# LED_Transmitter_2023_01_22_A.net
KiCad netlist of a schematic drawn in EAGLE
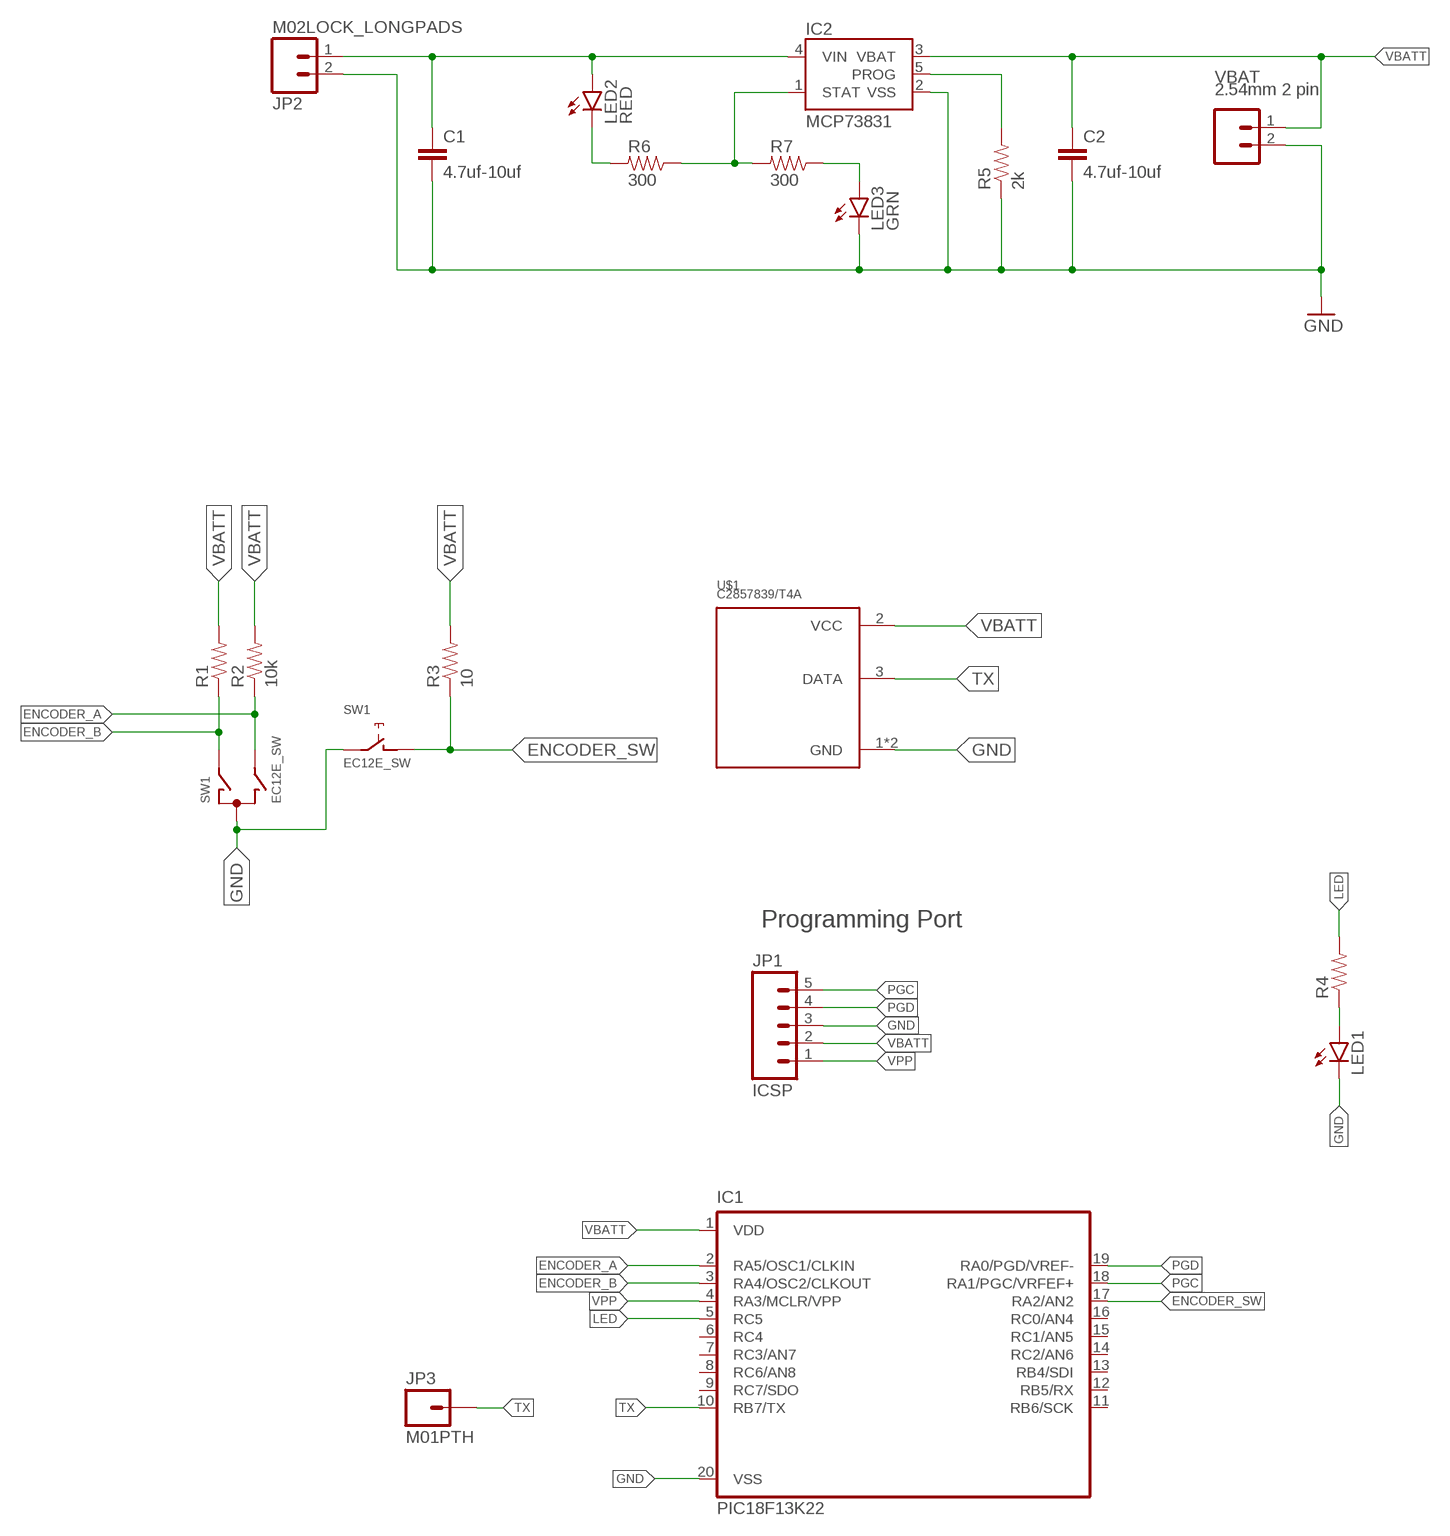
[diagram p0: schematic, sheet 1]

(export (version "E")
  (design (tool "Eeschema 10.0.6"))
  (components
    (comp (ref "C1")
      (value "4.7uf-10uf")
      (footprint "eagle-import:1206")
      (libsource (lib "eagle-import") (part "CAP1206"))
    )
    (comp (ref "C2")
      (value "4.7uf-10uf")
      (footprint "eagle-import:1206")
      (libsource (lib "eagle-import") (part "CAP1206"))
    )
    (comp (ref "IC1")
      (value "PIC18F13K22")
      (footprint "eagle-import:DIL20")
      (libsource (lib "eagle-import") (part "PIC18F13K22?"))
    )
    (comp (ref "IC2")
      (value "MCP73831")
      (footprint "eagle-import:SOT23-5")
      (libsource (lib "eagle-import") (part "MCP73831"))
    )
    (comp (ref "JP1")
      (value "ICSP")
      (footprint "eagle-import:1X05")
      (libsource (lib "eagle-import") (part "M05PTH"))
    )
    (comp (ref "JP2")
      (value "M02LOCK_LONGPADS")
      (footprint "eagle-import:1X02_LOCK_LONGPADS")
      (libsource (lib "eagle-import") (part "M02LOCK_LONGPADS"))
    )
    (comp (ref "JP3")
      (value "M01PTH")
      (footprint "eagle-import:1X01")
      (libsource (lib "eagle-import") (part "M01PTH"))
    )
    (comp (ref "LED1")
      (value "LED1206")
      (footprint "eagle-import:LED-1206")
      (libsource (lib "eagle-import") (part "LED1206"))
    )
    (comp (ref "LED2")
      (value "RED")
      (footprint "eagle-import:LED-1206")
      (libsource (lib "eagle-import") (part "LED1206"))
    )
    (comp (ref "LED3")
      (value "GRN")
      (footprint "eagle-import:LED-1206")
      (libsource (lib "eagle-import") (part "LED1206"))
    )
    (comp (ref "R1")
      (value "RESISTOR1206")
      (footprint "eagle-import:1206")
      (libsource (lib "eagle-import") (part "RESISTOR1206"))
    )
    (comp (ref "R2")
      (value "10k")
      (footprint "eagle-import:1206")
      (libsource (lib "eagle-import") (part "RESISTOR1206"))
    )
    (comp (ref "R3")
      (value "10")
      (footprint "eagle-import:1206")
      (libsource (lib "eagle-import") (part "RESISTOR1206"))
    )
    (comp (ref "R4")
      (value "RESISTOR1206")
      (footprint "eagle-import:1206")
      (libsource (lib "eagle-import") (part "RESISTOR1206"))
    )
    (comp (ref "R5")
      (value "2k")
      (footprint "eagle-import:1206")
      (libsource (lib "eagle-import") (part "RESISTOR1206"))
    )
    (comp (ref "R6")
      (value "300")
      (footprint "eagle-import:1206")
      (libsource (lib "eagle-import") (part "RESISTOR1206"))
    )
    (comp (ref "R7")
      (value "300")
      (footprint "eagle-import:1206")
      (libsource (lib "eagle-import") (part "RESISTOR1206"))
    )
    (comp (ref "SW1")
      (value "EC12E_SW")
      (footprint "eagle-import:ALPS_EC12E_SW")
      (fields (field (name "MPN") "EC12E2424407"))
      (libsource (lib "eagle-import") (part "EC12E_SW"))
    )
    (comp (ref "U$1")
      (value "C2857839/T4A")
      (footprint "eagle-import:1X04_LOCK_LONGPADS")
      (libsource (lib "eagle-import") (part "C2857839/T4A"))
    )
    (comp (ref "VBAT")
      (value "2.54mm 2 pin")
      (footprint "eagle-import:JST-2-PTH-VERT")
      (libsource (lib "eagle-import") (part "M02JST-PTH-VERT"))
    )
  )
  (nets
    (net (code "1") (name "ENCODER_A") (class "Default")
      (node (ref "IC1") (pin "2") (pinfunction "RA5/OSC1/CLKIN_2") (pintype "bidirectional"))
      (node (ref "R2") (pin "1") (pinfunction "1_1") (pintype "passive"))
      (node (ref "SW1") (pin "B") (pinfunction "B_B") (pintype "passive"))
    )
    (net (code "2") (name "ENCODER_B") (class "Default")
      (node (ref "IC1") (pin "3") (pinfunction "RA4/OSC2/CLKOUT_3") (pintype "bidirectional"))
      (node (ref "R1") (pin "1") (pinfunction "1_1") (pintype "passive"))
      (node (ref "SW1") (pin "A") (pinfunction "A_A") (pintype "passive"))
    )
    (net (code "3") (name "ENCODER_SW") (class "Default")
      (node (ref "IC1") (pin "17") (pinfunction "RA2/AN2_17") (pintype "bidirectional"))
      (node (ref "R3") (pin "1") (pinfunction "1_1") (pintype "passive"))
      (node (ref "SW1") (pin "D") (pinfunction "1_D") (pintype "passive"))
    )
    (net (code "4") (name "GND") (class "Default")
      (node (ref "C1") (pin "2") (pinfunction "2_2") (pintype "passive"))
      (node (ref "C2") (pin "2") (pinfunction "2_2") (pintype "passive"))
      (node (ref "IC1") (pin "20") (pinfunction "VSS_20") (pintype "power_in"))
      (node (ref "IC2") (pin "2") (pinfunction "VSS_2") (pintype "power_in"))
      (node (ref "JP1") (pin "3") (pinfunction "3_3") (pintype "passive"))
      (node (ref "JP2") (pin "2") (pinfunction "2_2") (pintype "passive"))
      (node (ref "LED1") (pin "C") (pinfunction "C_C") (pintype "passive"))
      (node (ref "LED3") (pin "C") (pinfunction "C_C") (pintype "passive"))
      (node (ref "R5") (pin "1") (pinfunction "1_1") (pintype "passive"))
      (node (ref "SW1") (pin "C") (pinfunction "C_C") (pintype "passive"))
      (node (ref "SW1") (pin "E") (pinfunction "2_E") (pintype "passive"))
      (node (ref "U$1") (pin "1") (pinfunction "GND_1") (pintype "bidirectional"))
      (node (ref "U$1") (pin "4") (pinfunction "GND_4") (pintype "bidirectional"))
      (node (ref "VBAT") (pin "2") (pinfunction "2_2") (pintype "passive"))
    )
    (net (code "5") (name "LED") (class "Default")
      (node (ref "IC1") (pin "5") (pinfunction "RC5_5") (pintype "bidirectional"))
      (node (ref "R4") (pin "2") (pinfunction "2_2") (pintype "passive"))
    )
    (net (code "6") (name "Net-(IC2-PROG)") (class "Default")
      (node (ref "IC2") (pin "5") (pinfunction "PROG_5") (pintype "input"))
      (node (ref "R5") (pin "2") (pinfunction "2_2") (pintype "passive"))
    )
    (net (code "7") (name "Net-(IC2-STAT)") (class "Default")
      (node (ref "IC2") (pin "1") (pinfunction "STAT_1") (pintype "output"))
      (node (ref "R6") (pin "1") (pinfunction "1_1") (pintype "passive"))
      (node (ref "R7") (pin "2") (pinfunction "2_2") (pintype "passive"))
    )
    (net (code "8") (name "Net-(IC2-VIN)") (class "Default")
      (node (ref "C1") (pin "1") (pinfunction "1_1") (pintype "passive"))
      (node (ref "IC2") (pin "4") (pinfunction "VIN_4") (pintype "power_in"))
      (node (ref "JP2") (pin "1") (pinfunction "1_1") (pintype "passive"))
      (node (ref "LED2") (pin "A") (pinfunction "A_A") (pintype "passive"))
    )
    (net (code "9") (name "Net-(LED1-PadA)") (class "Default")
      (node (ref "LED1") (pin "A") (pinfunction "A_A") (pintype "passive"))
      (node (ref "R4") (pin "1") (pinfunction "1_1") (pintype "passive"))
    )
    (net (code "10") (name "Net-(LED2-PadC)") (class "Default")
      (node (ref "LED2") (pin "C") (pinfunction "C_C") (pintype "passive"))
      (node (ref "R6") (pin "2") (pinfunction "2_2") (pintype "passive"))
    )
    (net (code "11") (name "Net-(LED3-PadA)") (class "Default")
      (node (ref "LED3") (pin "A") (pinfunction "A_A") (pintype "passive"))
      (node (ref "R7") (pin "1") (pinfunction "1_1") (pintype "passive"))
    )
    (net (code "12") (name "PGC") (class "Default")
      (node (ref "IC1") (pin "18") (pinfunction "RA1/PGC/VRFEF+_18") (pintype "bidirectional"))
      (node (ref "JP1") (pin "5") (pinfunction "5_5") (pintype "passive"))
    )
    (net (code "13") (name "PGD") (class "Default")
      (node (ref "IC1") (pin "19") (pinfunction "RA0/PGD/VREF-_19") (pintype "bidirectional"))
      (node (ref "JP1") (pin "4") (pinfunction "4_4") (pintype "passive"))
    )
    (net (code "14") (name "TX") (class "Default")
      (node (ref "IC1") (pin "10") (pinfunction "RB7/TX_10") (pintype "bidirectional"))
      (node (ref "JP3") (pin "1") (pinfunction "1_1") (pintype "passive"))
      (node (ref "U$1") (pin "3") (pinfunction "DATA_3") (pintype "bidirectional"))
    )
    (net (code "15") (name "VBATT") (class "Default")
      (node (ref "C2") (pin "1") (pinfunction "1_1") (pintype "passive"))
      (node (ref "IC1") (pin "1") (pinfunction "VDD_1") (pintype "power_in"))
      (node (ref "IC2") (pin "3") (pinfunction "VBAT_3") (pintype "power_in"))
      (node (ref "JP1") (pin "2") (pinfunction "2_2") (pintype "passive"))
      (node (ref "R1") (pin "2") (pinfunction "2_2") (pintype "passive"))
      (node (ref "R2") (pin "2") (pinfunction "2_2") (pintype "passive"))
      (node (ref "R3") (pin "2") (pinfunction "2_2") (pintype "passive"))
      (node (ref "U$1") (pin "2") (pinfunction "VCC_2") (pintype "bidirectional"))
      (node (ref "VBAT") (pin "1") (pinfunction "1_1") (pintype "passive"))
    )
    (net (code "16") (name "VPP") (class "Default")
      (node (ref "IC1") (pin "4") (pinfunction "RA3/MCLR/VPP_4") (pintype "bidirectional"))
      (node (ref "JP1") (pin "1") (pinfunction "1_1") (pintype "passive"))
    )
    (net (code "17") (name "unconnected-(IC1-RB4{slash}SDI-Pad13)") (class "Default")
      (node (ref "IC1") (pin "13") (pinfunction "RB4/SDI_13") (pintype "bidirectional"))
    )
    (net (code "18") (name "unconnected-(IC1-RB5{slash}RX-Pad12)") (class "Default")
      (node (ref "IC1") (pin "12") (pinfunction "RB5/RX_12") (pintype "bidirectional"))
    )
    (net (code "19") (name "unconnected-(IC1-RB6{slash}SCK-Pad11)") (class "Default")
      (node (ref "IC1") (pin "11") (pinfunction "RB6/SCK_11") (pintype "bidirectional"))
    )
    (net (code "20") (name "unconnected-(IC1-RC0{slash}AN4-Pad16)") (class "Default")
      (node (ref "IC1") (pin "16") (pinfunction "RC0/AN4_16") (pintype "bidirectional"))
    )
    (net (code "21") (name "unconnected-(IC1-RC1{slash}AN5-Pad15)") (class "Default")
      (node (ref "IC1") (pin "15") (pinfunction "RC1/AN5_15") (pintype "bidirectional"))
    )
    (net (code "22") (name "unconnected-(IC1-RC2{slash}AN6-Pad14)") (class "Default")
      (node (ref "IC1") (pin "14") (pinfunction "RC2/AN6_14") (pintype "bidirectional"))
    )
    (net (code "23") (name "unconnected-(IC1-RC3{slash}AN7-Pad7)") (class "Default")
      (node (ref "IC1") (pin "7") (pinfunction "RC3/AN7_7") (pintype "bidirectional"))
    )
    (net (code "24") (name "unconnected-(IC1-RC4-Pad6)") (class "Default")
      (node (ref "IC1") (pin "6") (pinfunction "RC4_6") (pintype "bidirectional"))
    )
    (net (code "25") (name "unconnected-(IC1-RC6{slash}AN8-Pad8)") (class "Default")
      (node (ref "IC1") (pin "8") (pinfunction "RC6/AN8_8") (pintype "bidirectional"))
    )
    (net (code "26") (name "unconnected-(IC1-RC7{slash}SDO-Pad9)") (class "Default")
      (node (ref "IC1") (pin "9") (pinfunction "RC7/SDO_9") (pintype "bidirectional"))
    )
  )
)
